# POWER_INPUT.net
KiCad netlist of a schematic drawn in Altium Designer
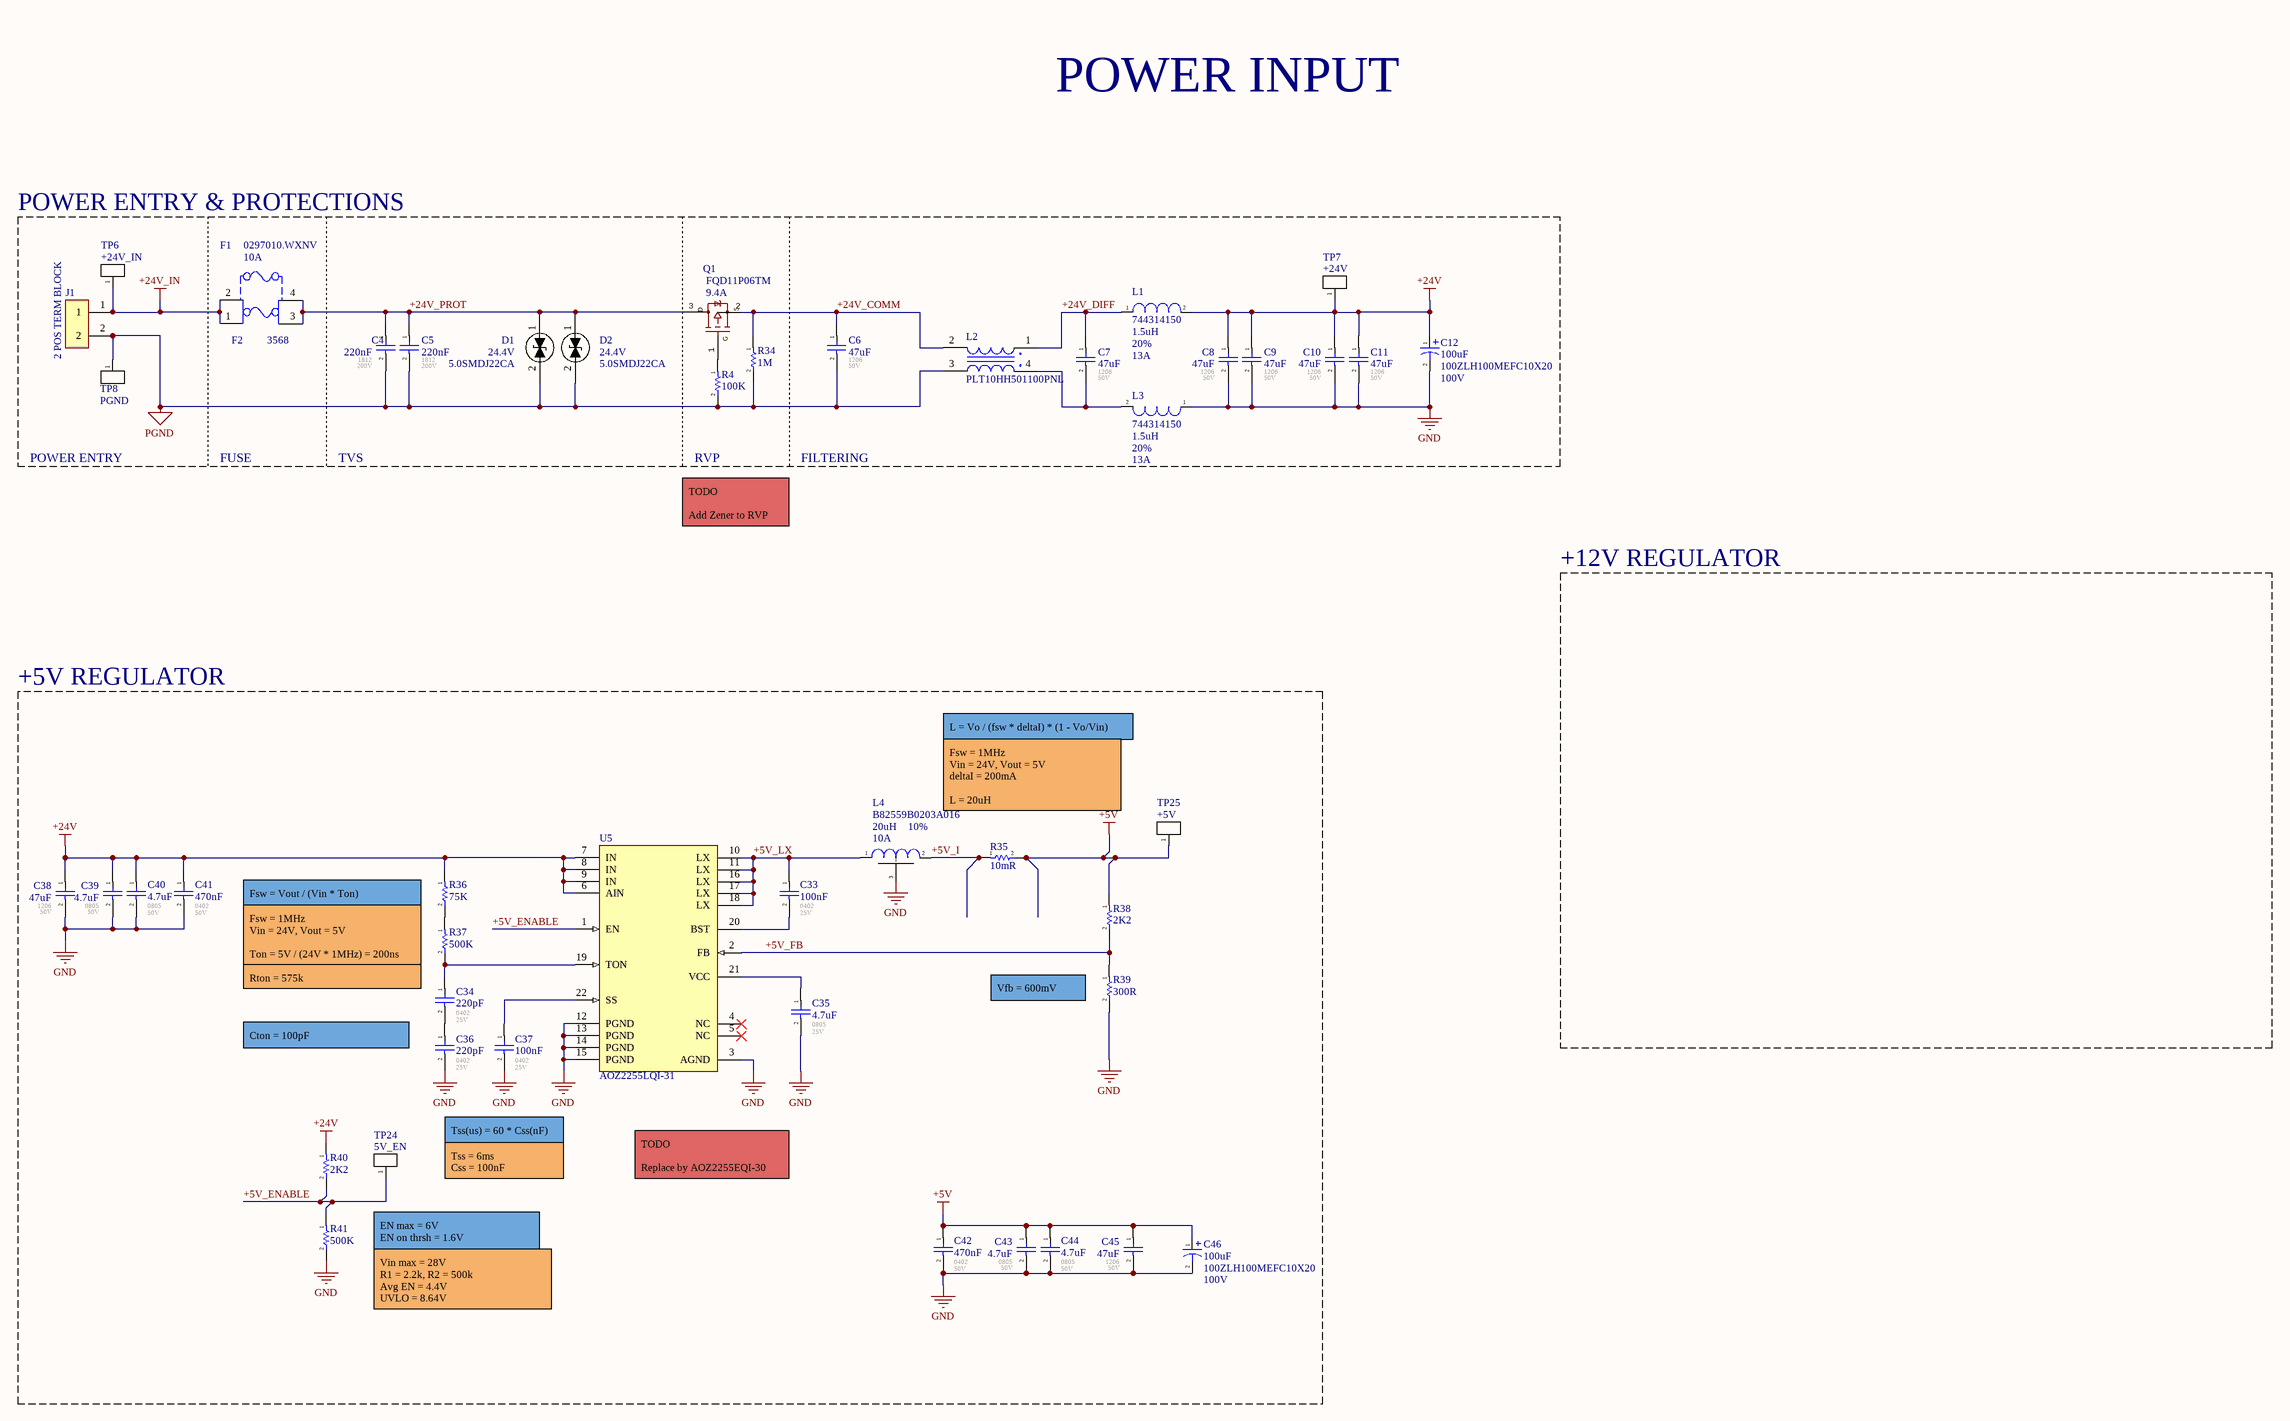
[diagram p0: POWER INPUT.SchDoc]

(export (version "E")
  (design (tool "Eeschema 10.0.6"))
  (components
    (comp (ref "C4")
      (value "220nF")
      (footprint "1812")
      (description "Generic SMT Ceramic Capacitor")
      (fields (field (name "VOLTAGE - RATED") "200V"))
      (libsource (lib "Symbols") (part "CAP_CER"))
    )
    (comp (ref "C5")
      (value "220nF")
      (footprint "1812")
      (description "Generic SMT Ceramic Capacitor")
      (fields (field (name "VOLTAGE - RATED") "200V"))
      (libsource (lib "Symbols") (part "CAP_CER"))
    )
    (comp (ref "C6")
      (value "47uF")
      (footprint "1206")
      (description "Generic SMT Ceramic Capacitor")
      (fields (field (name "VOLTAGE - RATED") "50V"))
      (libsource (lib "Symbols") (part "CAP_CER"))
    )
    (comp (ref "C7")
      (value "47uF")
      (footprint "1206")
      (description "Generic SMT Ceramic Capacitor")
      (fields (field (name "VOLTAGE - RATED") "50V"))
      (libsource (lib "Symbols") (part "CAP_CER"))
    )
    (comp (ref "C8")
      (value "47uF")
      (footprint "1206")
      (description "Generic SMT Ceramic Capacitor")
      (fields (field (name "VOLTAGE - RATED") "50V"))
      (libsource (lib "Symbols") (part "CAP_CER"))
    )
    (comp (ref "C9")
      (value "47uF")
      (footprint "1206")
      (description "Generic SMT Ceramic Capacitor")
      (fields (field (name "VOLTAGE - RATED") "50V"))
      (libsource (lib "Symbols") (part "CAP_CER"))
    )
    (comp (ref "C10")
      (value "47uF")
      (footprint "1206")
      (description "Generic SMT Ceramic Capacitor")
      (fields (field (name "VOLTAGE - RATED") "50V"))
      (libsource (lib "Symbols") (part "CAP_CER"))
    )
    (comp (ref "C11")
      (value "47uF")
      (footprint "1206")
      (description "Generic SMT Ceramic Capacitor")
      (fields (field (name "VOLTAGE - RATED") "50V"))
      (libsource (lib "Symbols") (part "CAP_CER"))
    )
    (comp (ref "C12")
      (value "100uF")
      (footprint "100ZLH100MEFC10X20")
      (description "CAP 100uF 20% 100V T/H")
      (fields
        (field (name "MFR") "Rubycon")
        (field (name "TOLERANCE") "20%")
        (field (name "MANUFACTURER PART NUMBER") "100ZLH100MEFC10X20")
        (field (name "RATED VOLTAGE") "100V")
        (field (name "CREATED BY") "Pascal-Emmanuel Lachance")
      )
      (libsource (lib "CryptLib") (part "CAP_100ZLH100MEFC10X20"))
    )
    (comp (ref "C33")
      (value "100nF")
      (footprint "0402")
      (description "Generic SMT Ceramic Capacitor")
      (fields (field (name "VOLTAGE - RATED") "25V"))
      (libsource (lib "Symbols") (part "CAP_CER"))
    )
    (comp (ref "C34")
      (value "220pF")
      (footprint "0402")
      (description "Generic SMT Ceramic Capacitor")
      (fields (field (name "VOLTAGE - RATED") "25V"))
      (libsource (lib "Symbols") (part "CAP_CER"))
    )
    (comp (ref "C35")
      (value "4.7uF")
      (footprint "0805")
      (description "Generic SMT Ceramic Capacitor")
      (fields (field (name "VOLTAGE - RATED") "25V"))
      (libsource (lib "Symbols") (part "CAP_CER"))
    )
    (comp (ref "C36")
      (value "220pF")
      (footprint "0402")
      (description "Generic SMT Ceramic Capacitor")
      (fields (field (name "VOLTAGE - RATED") "25V"))
      (libsource (lib "Symbols") (part "CAP_CER"))
    )
    (comp (ref "C37")
      (value "100nF")
      (footprint "0402")
      (description "Generic SMT Ceramic Capacitor")
      (fields (field (name "VOLTAGE - RATED") "25V"))
      (libsource (lib "Symbols") (part "CAP_CER"))
    )
    (comp (ref "C38")
      (value "47uF")
      (footprint "1206")
      (description "Generic SMT Ceramic Capacitor")
      (fields (field (name "VOLTAGE - RATED") "50V"))
      (libsource (lib "Symbols") (part "CAP_CER"))
    )
    (comp (ref "C39")
      (value "4.7uF")
      (footprint "0805")
      (description "Generic SMT Ceramic Capacitor")
      (fields (field (name "VOLTAGE - RATED") "50V"))
      (libsource (lib "Symbols") (part "CAP_CER"))
    )
    (comp (ref "C40")
      (value "4.7uF")
      (footprint "0805")
      (description "Generic SMT Ceramic Capacitor")
      (fields (field (name "VOLTAGE - RATED") "50V"))
      (libsource (lib "Symbols") (part "CAP_CER"))
    )
    (comp (ref "C41")
      (value "470nF")
      (footprint "0402")
      (description "Generic SMT Ceramic Capacitor")
      (fields (field (name "VOLTAGE - RATED") "50V"))
      (libsource (lib "Symbols") (part "CAP_CER"))
    )
    (comp (ref "C42")
      (value "470nF")
      (footprint "0402")
      (description "Generic SMT Ceramic Capacitor")
      (fields (field (name "VOLTAGE - RATED") "50V"))
      (libsource (lib "Symbols") (part "CAP_CER"))
    )
    (comp (ref "C43")
      (value "4.7uF")
      (footprint "0805")
      (description "Generic SMT Ceramic Capacitor")
      (fields (field (name "VOLTAGE - RATED") "50V"))
      (libsource (lib "Symbols") (part "CAP_CER"))
    )
    (comp (ref "C44")
      (value "4.7uF")
      (footprint "0805")
      (description "Generic SMT Ceramic Capacitor")
      (fields (field (name "VOLTAGE - RATED") "50V"))
      (libsource (lib "Symbols") (part "CAP_CER"))
    )
    (comp (ref "C45")
      (value "47uF")
      (footprint "1206")
      (description "Generic SMT Ceramic Capacitor")
      (fields (field (name "VOLTAGE - RATED") "50V"))
      (libsource (lib "Symbols") (part "CAP_CER"))
    )
    (comp (ref "C46")
      (value "100uF")
      (footprint "100ZLH100MEFC10X20")
      (description "CAP 100uF 20% 100V T/H")
      (fields
        (field (name "MFR") "Rubycon")
        (field (name "TOLERANCE") "20%")
        (field (name "MANUFACTURER PART NUMBER") "100ZLH100MEFC10X20")
        (field (name "RATED VOLTAGE") "100V")
        (field (name "CREATED BY") "Pascal-Emmanuel Lachance")
      )
      (libsource (lib "CryptLib") (part "CAP_100ZLH100MEFC10X20"))
    )
    (comp (ref "D1")
      (value "5.0SMDJ22CA")
      (footprint "DO214AB (SMC)")
      (description "TVS Diode 24.4V")
      (fields
        (field (name "MFR") "Littelfuse")
        (field (name "VOLTAGE - BREAKDOWN") "24.4V")
        (field (name "CREATED BY") "Pascal-Emmanuel Lachance")
      )
      (libsource (lib "CryptLib") (part "DIODE_5.0SMDJ22CA"))
    )
    (comp (ref "D2")
      (value "5.0SMDJ22CA")
      (footprint "DO214AB (SMC)")
      (description "TVS Diode 24.4V")
      (fields
        (field (name "MFR") "Littelfuse")
        (field (name "VOLTAGE - BREAKDOWN") "24.4V")
        (field (name "CREATED BY") "Pascal-Emmanuel Lachance")
      )
      (libsource (lib "CryptLib") (part "DIODE_5.0SMDJ22CA"))
    )
    (comp (ref "F1")
      (value "0297010.WXNV")
      (footprint "0297010.WXNV")
      (description "FUSE AUTO 10A 32V BLADE MINI")
      (fields
        (field (name "MFR") "Littelfuse")
        (field (name "CURRENT - TRIP") "10A")
        (field (name "CREATED BY") "Pascal-Emmanuel Lachance")
      )
      (libsource (lib "CryptLib") (part "FUSE_0297010.WXNV"))
    )
    (comp (ref "F2")
      (value "3568")
      (footprint "3568")
      (description "FUSE HOLDER BLADE")
      (fields (field (name "MFR") "Keystone") (field (name "CREATED BY") "Pascal-Emmanuel Lachance"))
      (libsource (lib "CryptLib") (part "FUSE_HOLDER_3568"))
    )
    (comp (ref "J1")
      (value "2 POS TERM BLOCK")
      (footprint "TERM-2_90_100MIL")
      (libsource (lib "Connectors") (part "TERM_BLOCK-2"))
    )
    (comp (ref "L1")
      (value "744314150")
      (footprint "744314150")
      (description "FIXED IND 1.5UH 13A 4.3 MOHM SMD")
      (fields
        (field (name "MFR") "Wurth")
        (field (name "INDUCTANCE") "1.5uH")
        (field (name "TOLERANCE") "20%")
        (field (name "CURRENT RATING") "13A")
        (field (name "CREATED BY") "Pascal-Emmanuel Lachance")
      )
      (libsource (lib "CryptLib") (part "IND_744314150"))
    )
    (comp (ref "L2")
      (value "PLT10HH501100PNL")
      (footprint "PLT10HH501100PNL")
      (description "2 Line Common Mode Choke Surface Mount 500 Ohms @ 10MHz 10A DCR 4.1mOhm")
      (fields (field (name "MFR") "Murata") (field (name "CREATED BY") "Pascal-Emmanuel Lachance"))
      (libsource (lib "CryptLib") (part "IND_PLT10HH501100PNL"))
    )
    (comp (ref "L3")
      (value "744314150")
      (footprint "744314150")
      (description "FIXED IND 1.5UH 13A 4.3 MOHM SMD")
      (fields
        (field (name "MFR") "Wurth")
        (field (name "INDUCTANCE") "1.5uH")
        (field (name "TOLERANCE") "20%")
        (field (name "CURRENT RATING") "13A")
        (field (name "CREATED BY") "Pascal-Emmanuel Lachance")
      )
      (libsource (lib "CryptLib") (part "IND_744314150"))
    )
    (comp (ref "L4")
      (value "B82559B0203A016")
      (footprint "B82559B0203A016")
      (description "20uH Shielded 10A Inductor")
      (fields
        (field (name "MFR") "TDK")
        (field (name "INDUCTANCE") "20uH")
        (field (name "TOLERANCE") "10%")
        (field (name "CURRENT RATING") "10A")
        (field (name "CREATED BY") "Pascal-Emmanuel Lachance")
      )
      (libsource (lib "CryptLib") (part "IND_B82559B0203A016"))
    )
    (comp (ref "Q1")
      (value "FQD11P06TM")
      (footprint "FQD11P06TM")
      (description "MOSFET P-CH 60V 9.4A DPAK")
      (fields
        (field (name "MFR") "ON Semiconductor")
        (field (name "DIGIKEY PART NUMBER") "FQD11P06TMCT-ND")
        (field (name "CURRENT") "9.4A")
      )
      (libsource (lib "CryptLib") (part "TRANS_FQD11P06TM"))
    )
    (comp (ref "R4")
      (value "100K")
      (footprint "RES_0603")
      (description "Resistor")
      (fields (field (name "POWER") "1/16W") (field (name "TOLERANCE") "10%"))
      (libsource (lib "Symbols") (part "RESISTOR"))
    )
    (comp (ref "R34")
      (value "1M")
      (footprint "RES_0402")
      (description "Resistor")
      (fields (field (name "POWER") "1/16W") (field (name "TOLERANCE") "10%"))
      (libsource (lib "Symbols") (part "RESISTOR"))
    )
    (comp (ref "R35")
      (value "10mR")
      (footprint "RES_2512")
      (description "Resistor")
      (fields (field (name "POWER") "2W") (field (name "TOLERANCE") "1%"))
      (libsource (lib "Symbols") (part "RESISTOR"))
    )
    (comp (ref "R36")
      (value "75K")
      (footprint "RES_0402")
      (description "Resistor")
      (fields (field (name "POWER") "1/10W") (field (name "TOLERANCE") "10%"))
      (libsource (lib "Symbols") (part "RESISTOR"))
    )
    (comp (ref "R37")
      (value "500K")
      (footprint "RES_0402")
      (description "Resistor")
      (fields (field (name "POWER") "1/10W") (field (name "TOLERANCE") "10%"))
      (libsource (lib "Symbols") (part "RESISTOR"))
    )
    (comp (ref "R38")
      (value "2K2")
      (footprint "RES_0603")
      (description "Resistor")
      (fields (field (name "POWER") "1/16W") (field (name "TOLERANCE") "2%"))
      (libsource (lib "Symbols") (part "RESISTOR"))
    )
    (comp (ref "R39")
      (value "300R")
      (footprint "RES_0603")
      (description "Resistor")
      (fields (field (name "POWER") "1/8W") (field (name "TOLERANCE") "2%"))
      (libsource (lib "Symbols") (part "RESISTOR"))
    )
    (comp (ref "R40")
      (value "2K2")
      (footprint "RES_0603")
      (description "Resistor")
      (fields (field (name "POWER") "1/16W") (field (name "TOLERANCE") "2%"))
      (libsource (lib "Symbols") (part "RESISTOR"))
    )
    (comp (ref "R41")
      (value "500K")
      (footprint "RES_0402")
      (description "Resistor")
      (fields (field (name "POWER") "1/10W") (field (name "TOLERANCE") "10%"))
      (libsource (lib "Symbols") (part "RESISTOR"))
    )
    (comp (ref "TP6")
      (value "+24V_IN")
      (footprint "TP_HOLE")
      (description "Test Point")
      (libsource (lib "Symbols") (part "TESTPOINT"))
    )
    (comp (ref "TP7")
      (value "+24V")
      (footprint "TP_HOLE")
      (description "Test Point")
      (libsource (lib "Symbols") (part "TESTPOINT"))
    )
    (comp (ref "TP8")
      (value "PGND")
      (footprint "TP_HOLE")
      (description "Test Point")
      (libsource (lib "Symbols") (part "TESTPOINT"))
    )
    (comp (ref "TP24")
      (value "5V_EN")
      (footprint "TP_PAD_SMALL")
      (description "Test Point")
      (libsource (lib "Symbols") (part "TESTPOINT"))
    )
    (comp (ref "TP25")
      (value "+5V")
      (footprint "TP_HOLE")
      (description "Test Point")
      (libsource (lib "Symbols") (part "TESTPOINT"))
    )
    (comp (ref "U5")
      (value "AOZ2255LQI-31")
      (footprint "AOZ2255LQI-31")
      (description "Buck Switching Regulator IC Positive Adjustable 0.6V 1 Output 12A 22-PowerVFQFN")
      (fields (field (name "MFR") "Alpha & Omega Semiconductor"))
      (libsource (lib "CryptLib") (part "IC_AOZ2255LQI-31"))
    )
  )
  (nets
    (net (code "1") (name "+5V") (class "Default")
      (node (ref "C42") (pin "1") (pinfunction "1_1") (pintype "passive"))
      (node (ref "C43") (pin "1") (pinfunction "1_1") (pintype "passive"))
      (node (ref "C44") (pin "1") (pinfunction "1_1") (pintype "passive"))
      (node (ref "C45") (pin "1") (pinfunction "1_1") (pintype "passive"))
      (node (ref "C46") (pin "1") (pinfunction "1_1") (pintype "passive"))
      (node (ref "R35") (pin "2") (pinfunction "2_2") (pintype "passive"))
      (node (ref "R38") (pin "1") (pinfunction "1_1") (pintype "passive"))
      (node (ref "TP25") (pin "1") (pinfunction "A_1") (pintype "passive"))
    )
    (net (code "2") (name "+24V") (class "Default")
      (node (ref "C10") (pin "1") (pinfunction "1_1") (pintype "passive"))
      (node (ref "C11") (pin "1") (pinfunction "1_1") (pintype "passive"))
      (node (ref "C12") (pin "1") (pinfunction "1_1") (pintype "passive"))
      (node (ref "C38") (pin "1") (pinfunction "1_1") (pintype "passive"))
      (node (ref "C39") (pin "1") (pinfunction "1_1") (pintype "passive"))
      (node (ref "C40") (pin "1") (pinfunction "1_1") (pintype "passive"))
      (node (ref "C41") (pin "1") (pinfunction "1_1") (pintype "passive"))
      (node (ref "C8") (pin "1") (pinfunction "1_1") (pintype "passive"))
      (node (ref "C9") (pin "1") (pinfunction "1_1") (pintype "passive"))
      (node (ref "L1") (pin "2") (pinfunction "2_2") (pintype "passive"))
      (node (ref "R36") (pin "1") (pinfunction "1_1") (pintype "passive"))
      (node (ref "R40") (pin "1") (pinfunction "1_1") (pintype "passive"))
      (node (ref "TP7") (pin "1") (pinfunction "A_1") (pintype "passive"))
      (node (ref "U5") (pin "6") (pinfunction "AIN_6") (pintype "power_in"))
      (node (ref "U5") (pin "7") (pinfunction "IN_7") (pintype "power_in"))
      (node (ref "U5") (pin "8") (pinfunction "IN_8") (pintype "power_in"))
      (node (ref "U5") (pin "9") (pinfunction "IN_9") (pintype "power_in"))
    )
    (net (code "3") (name "+24V_IN") (class "Default")
      (node (ref "F2") (pin "1") (pinfunction "1_1") (pintype "passive"))
      (node (ref "F2") (pin "2") (pinfunction "2_2") (pintype "passive"))
      (node (ref "J1") (pin "1") (pinfunction "1_1") (pintype "passive"))
      (node (ref "TP6") (pin "1") (pinfunction "A_1") (pintype "passive"))
    )
    (net (code "4") (name "/+5V_ENABLE") (class "Default")
      (node (ref "R40") (pin "2") (pinfunction "2_2") (pintype "passive"))
      (node (ref "R41") (pin "1") (pinfunction "1_1") (pintype "passive"))
      (node (ref "TP24") (pin "1") (pinfunction "A_1") (pintype "passive"))
      (node (ref "U5") (pin "1") (pinfunction "EN_1") (pintype "input"))
    )
    (net (code "5") (name "/+5V_FB") (class "Default")
      (node (ref "R38") (pin "2") (pinfunction "2_2") (pintype "passive"))
      (node (ref "R39") (pin "1") (pinfunction "1_1") (pintype "passive"))
      (node (ref "U5") (pin "2") (pinfunction "FB_2") (pintype "input"))
    )
    (net (code "6") (name "/+5V_I") (class "Default")
      (node (ref "L4") (pin "2") (pinfunction "2_2") (pintype "passive"))
      (node (ref "R35") (pin "1") (pinfunction "1_1") (pintype "passive"))
    )
    (net (code "7") (name "/+5V_LX") (class "Default")
      (node (ref "C33") (pin "1") (pinfunction "1_1") (pintype "passive"))
      (node (ref "L4") (pin "1") (pinfunction "1_1") (pintype "passive"))
      (node (ref "U5") (pin "10") (pinfunction "LX_10") (pintype "passive"))
      (node (ref "U5") (pin "11") (pinfunction "LX_11") (pintype "passive"))
      (node (ref "U5") (pin "16") (pinfunction "LX_16") (pintype "passive"))
      (node (ref "U5") (pin "17") (pinfunction "LX_17") (pintype "passive"))
      (node (ref "U5") (pin "18") (pinfunction "LX_18") (pintype "passive"))
    )
    (net (code "8") (name "/+24V_COMM") (class "Default")
      (node (ref "C6") (pin "1") (pinfunction "1_1") (pintype "passive"))
      (node (ref "L2") (pin "2") (pinfunction "2_2") (pintype "passive"))
      (node (ref "Q1") (pin "2") (pinfunction "S_2") (pintype "passive"))
      (node (ref "R34") (pin "1") (pinfunction "1_1") (pintype "passive"))
    )
    (net (code "9") (name "/+24V_DIFF") (class "Default")
      (node (ref "C7") (pin "1") (pinfunction "1_1") (pintype "passive"))
      (node (ref "L1") (pin "1") (pinfunction "1_1") (pintype "passive"))
      (node (ref "L2") (pin "1") (pinfunction "1_1") (pintype "passive"))
    )
    (net (code "10") (name "/+24V_PROT") (class "Default")
      (node (ref "C4") (pin "1") (pinfunction "1_1") (pintype "passive"))
      (node (ref "C5") (pin "1") (pinfunction "1_1") (pintype "passive"))
      (node (ref "D1") (pin "1") (pinfunction "A_1") (pintype "passive"))
      (node (ref "D2") (pin "1") (pinfunction "A_1") (pintype "passive"))
      (node (ref "F2") (pin "3") (pinfunction "3_3") (pintype "passive"))
      (node (ref "F2") (pin "4") (pinfunction "4_4") (pintype "passive"))
      (node (ref "Q1") (pin "3") (pinfunction "D_3") (pintype "passive"))
    )
    (net (code "11") (name "GND") (class "Default")
      (node (ref "C10") (pin "2") (pinfunction "2_2") (pintype "passive"))
      (node (ref "C11") (pin "2") (pinfunction "2_2") (pintype "passive"))
      (node (ref "C12") (pin "2") (pinfunction "2_2") (pintype "passive"))
      (node (ref "C35") (pin "2") (pinfunction "2_2") (pintype "passive"))
      (node (ref "C36") (pin "2") (pinfunction "2_2") (pintype "passive"))
      (node (ref "C37") (pin "2") (pinfunction "2_2") (pintype "passive"))
      (node (ref "C38") (pin "2") (pinfunction "2_2") (pintype "passive"))
      (node (ref "C39") (pin "2") (pinfunction "2_2") (pintype "passive"))
      (node (ref "C40") (pin "2") (pinfunction "2_2") (pintype "passive"))
      (node (ref "C41") (pin "2") (pinfunction "2_2") (pintype "passive"))
      (node (ref "C42") (pin "2") (pinfunction "2_2") (pintype "passive"))
      (node (ref "C43") (pin "2") (pinfunction "2_2") (pintype "passive"))
      (node (ref "C44") (pin "2") (pinfunction "2_2") (pintype "passive"))
      (node (ref "C45") (pin "2") (pinfunction "2_2") (pintype "passive"))
      (node (ref "C46") (pin "2") (pinfunction "2_2") (pintype "passive"))
      (node (ref "C8") (pin "2") (pinfunction "2_2") (pintype "passive"))
      (node (ref "C9") (pin "2") (pinfunction "2_2") (pintype "passive"))
      (node (ref "L3") (pin "1") (pinfunction "1_1") (pintype "passive"))
      (node (ref "L4") (pin "3") (pinfunction "SHIELD_3") (pintype "passive"))
      (node (ref "R39") (pin "2") (pinfunction "2_2") (pintype "passive"))
      (node (ref "R41") (pin "2") (pinfunction "2_2") (pintype "passive"))
      (node (ref "U5") (pin "12") (pinfunction "PGND_12") (pintype "power_in"))
      (node (ref "U5") (pin "13") (pinfunction "PGND_13") (pintype "power_in"))
      (node (ref "U5") (pin "14") (pinfunction "PGND_14") (pintype "power_in"))
      (node (ref "U5") (pin "15") (pinfunction "PGND_15") (pintype "power_in"))
      (node (ref "U5") (pin "3") (pinfunction "AGND_3") (pintype "power_in"))
    )
    (net (code "12") (name "Net-(C7-Pad2)") (class "Default")
      (node (ref "C7") (pin "2") (pinfunction "2_2") (pintype "passive"))
      (node (ref "L2") (pin "4") (pinfunction "4_4") (pintype "passive"))
      (node (ref "L3") (pin "2") (pinfunction "2_2") (pintype "passive"))
    )
    (net (code "13") (name "Net-(C34-Pad2)") (class "Default")
      (node (ref "C34") (pin "2") (pinfunction "2_2") (pintype "passive"))
      (node (ref "C36") (pin "1") (pinfunction "1_1") (pintype "passive"))
    )
    (net (code "14") (name "Net-(Q1-G)") (class "Default")
      (node (ref "Q1") (pin "1") (pinfunction "G_1") (pintype "passive"))
      (node (ref "R4") (pin "1") (pinfunction "1_1") (pintype "passive"))
    )
    (net (code "15") (name "Net-(R36-Pad2)") (class "Default")
      (node (ref "R36") (pin "2") (pinfunction "2_2") (pintype "passive"))
      (node (ref "R37") (pin "1") (pinfunction "1_1") (pintype "passive"))
    )
    (net (code "16") (name "Net-(U5-BST)") (class "Default")
      (node (ref "C33") (pin "2") (pinfunction "2_2") (pintype "passive"))
      (node (ref "U5") (pin "20") (pinfunction "BST_20") (pintype "passive"))
    )
    (net (code "17") (name "Net-(U5-SS)") (class "Default")
      (node (ref "C37") (pin "1") (pinfunction "1_1") (pintype "passive"))
      (node (ref "U5") (pin "22") (pinfunction "SS_22") (pintype "input"))
    )
    (net (code "18") (name "Net-(U5-TON)") (class "Default")
      (node (ref "C34") (pin "1") (pinfunction "1_1") (pintype "passive"))
      (node (ref "R37") (pin "2") (pinfunction "2_2") (pintype "passive"))
      (node (ref "U5") (pin "19") (pinfunction "TON_19") (pintype "input"))
    )
    (net (code "19") (name "Net-(U5-VCC)") (class "Default")
      (node (ref "C35") (pin "1") (pinfunction "1_1") (pintype "passive"))
      (node (ref "U5") (pin "21") (pinfunction "VCC_21") (pintype "power_in"))
    )
    (net (code "20") (name "PGND") (class "Default")
      (node (ref "C4") (pin "2") (pinfunction "2_2") (pintype "passive"))
      (node (ref "C5") (pin "2") (pinfunction "2_2") (pintype "passive"))
      (node (ref "C6") (pin "2") (pinfunction "2_2") (pintype "passive"))
      (node (ref "D1") (pin "2") (pinfunction "C_2") (pintype "passive"))
      (node (ref "D2") (pin "2") (pinfunction "C_2") (pintype "passive"))
      (node (ref "J1") (pin "2") (pinfunction "2_2") (pintype "passive"))
      (node (ref "L2") (pin "3") (pinfunction "3_3") (pintype "passive"))
      (node (ref "R34") (pin "2") (pinfunction "2_2") (pintype "passive"))
      (node (ref "R4") (pin "2") (pinfunction "2_2") (pintype "passive"))
      (node (ref "TP8") (pin "1") (pinfunction "A_1") (pintype "passive"))
    )
    (net (code "21") (name "unconnected-(U5-NC-Pad4)") (class "Default")
      (node (ref "U5") (pin "4") (pinfunction "NC_4") (pintype "passive+no_connect"))
    )
    (net (code "22") (name "unconnected-(U5-NC-Pad5)") (class "Default")
      (node (ref "U5") (pin "5") (pinfunction "NC_5") (pintype "passive+no_connect"))
    )
  )
)
